# Buffer.net
KiCad netlist of a schematic drawn in EAGLE
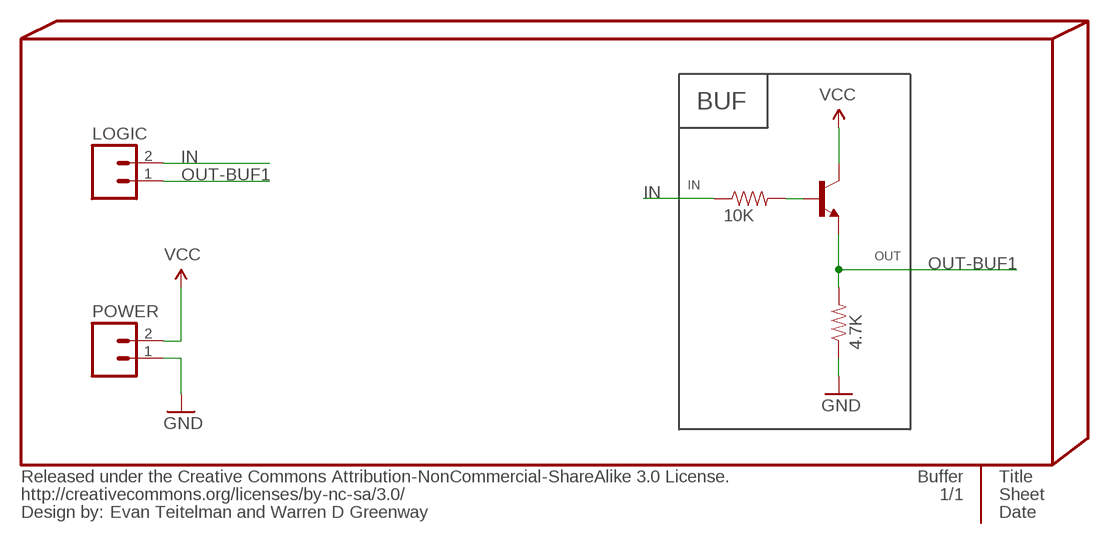
[diagram p0: schematic, sheet 1]

(export (version "E")
  (design (tool "Eeschema 10.0.6"))
  (components
    (comp (ref "INFO4")
      (value "Evan Teitelman and Warren D Greenway")
      (footprint "eagle-import:%CC-NC-SA")
      (libsource (lib "eagle-import") (part "%CC-NC-SA"))
    )
    (comp (ref "LOGIC")
      (value "M02PTH")
      (footprint "eagle-import:1X02")
      (libsource (lib "eagle-import") (part "M02PTH"))
    )
    (comp (ref "PDR-BUF1")
      (value "4.7K")
      (footprint "eagle-import:0402-RES")
      (libsource (lib "eagle-import") (part "RESISTOR0402-RES"))
    )
    (comp (ref "POWER")
      (value "M02PTH")
      (footprint "eagle-import:1X02")
      (libsource (lib "eagle-import") (part "M02PTH"))
    )
    (comp (ref "Q-BUF1")
      (value "TRANSISTOR_NPNSOT23")
      (footprint "eagle-import:SOT23")
      (libsource (lib "eagle-import") (part "TRANSISTOR_NPNSOT23"))
    )
    (comp (ref "R-BUF1")
      (value "10K")
      (footprint "eagle-import:0402-RES")
      (libsource (lib "eagle-import") (part "RESISTOR0402-RES"))
    )
  )
  (nets
    (net (code "1") (name "/IN") (class "Default")
      (node (ref "LOGIC") (pin "2") (pinfunction "2_2") (pintype "passive"))
      (node (ref "R-BUF1") (pin "1") (pinfunction "1_1") (pintype "passive"))
    )
    (net (code "2") (name "/OUT-BUF1") (class "Default")
      (node (ref "LOGIC") (pin "1") (pinfunction "1_1") (pintype "passive"))
      (node (ref "PDR-BUF1") (pin "2") (pinfunction "2_2") (pintype "passive"))
      (node (ref "Q-BUF1") (pin "2") (pinfunction "E_2") (pintype "passive"))
    )
    (net (code "3") (name "@GND") (class "Default")
      (node (ref "PDR-BUF1") (pin "1") (pinfunction "1_1") (pintype "passive"))
      (node (ref "POWER") (pin "1") (pinfunction "1_1") (pintype "passive"))
    )
    (net (code "4") (name "@VCC") (class "Default")
      (node (ref "POWER") (pin "2") (pinfunction "2_2") (pintype "passive"))
      (node (ref "Q-BUF1") (pin "3") (pinfunction "C_3") (pintype "passive"))
    )
    (net (code "5") (name "Net-(Q-BUF1-B)") (class "Default")
      (node (ref "Q-BUF1") (pin "1") (pinfunction "B_1") (pintype "passive"))
      (node (ref "R-BUF1") (pin "2") (pinfunction "2_2") (pintype "passive"))
    )
  )
)
